# uINS_Mk1.net
KiCad netlist of a schematic drawn in EAGLE
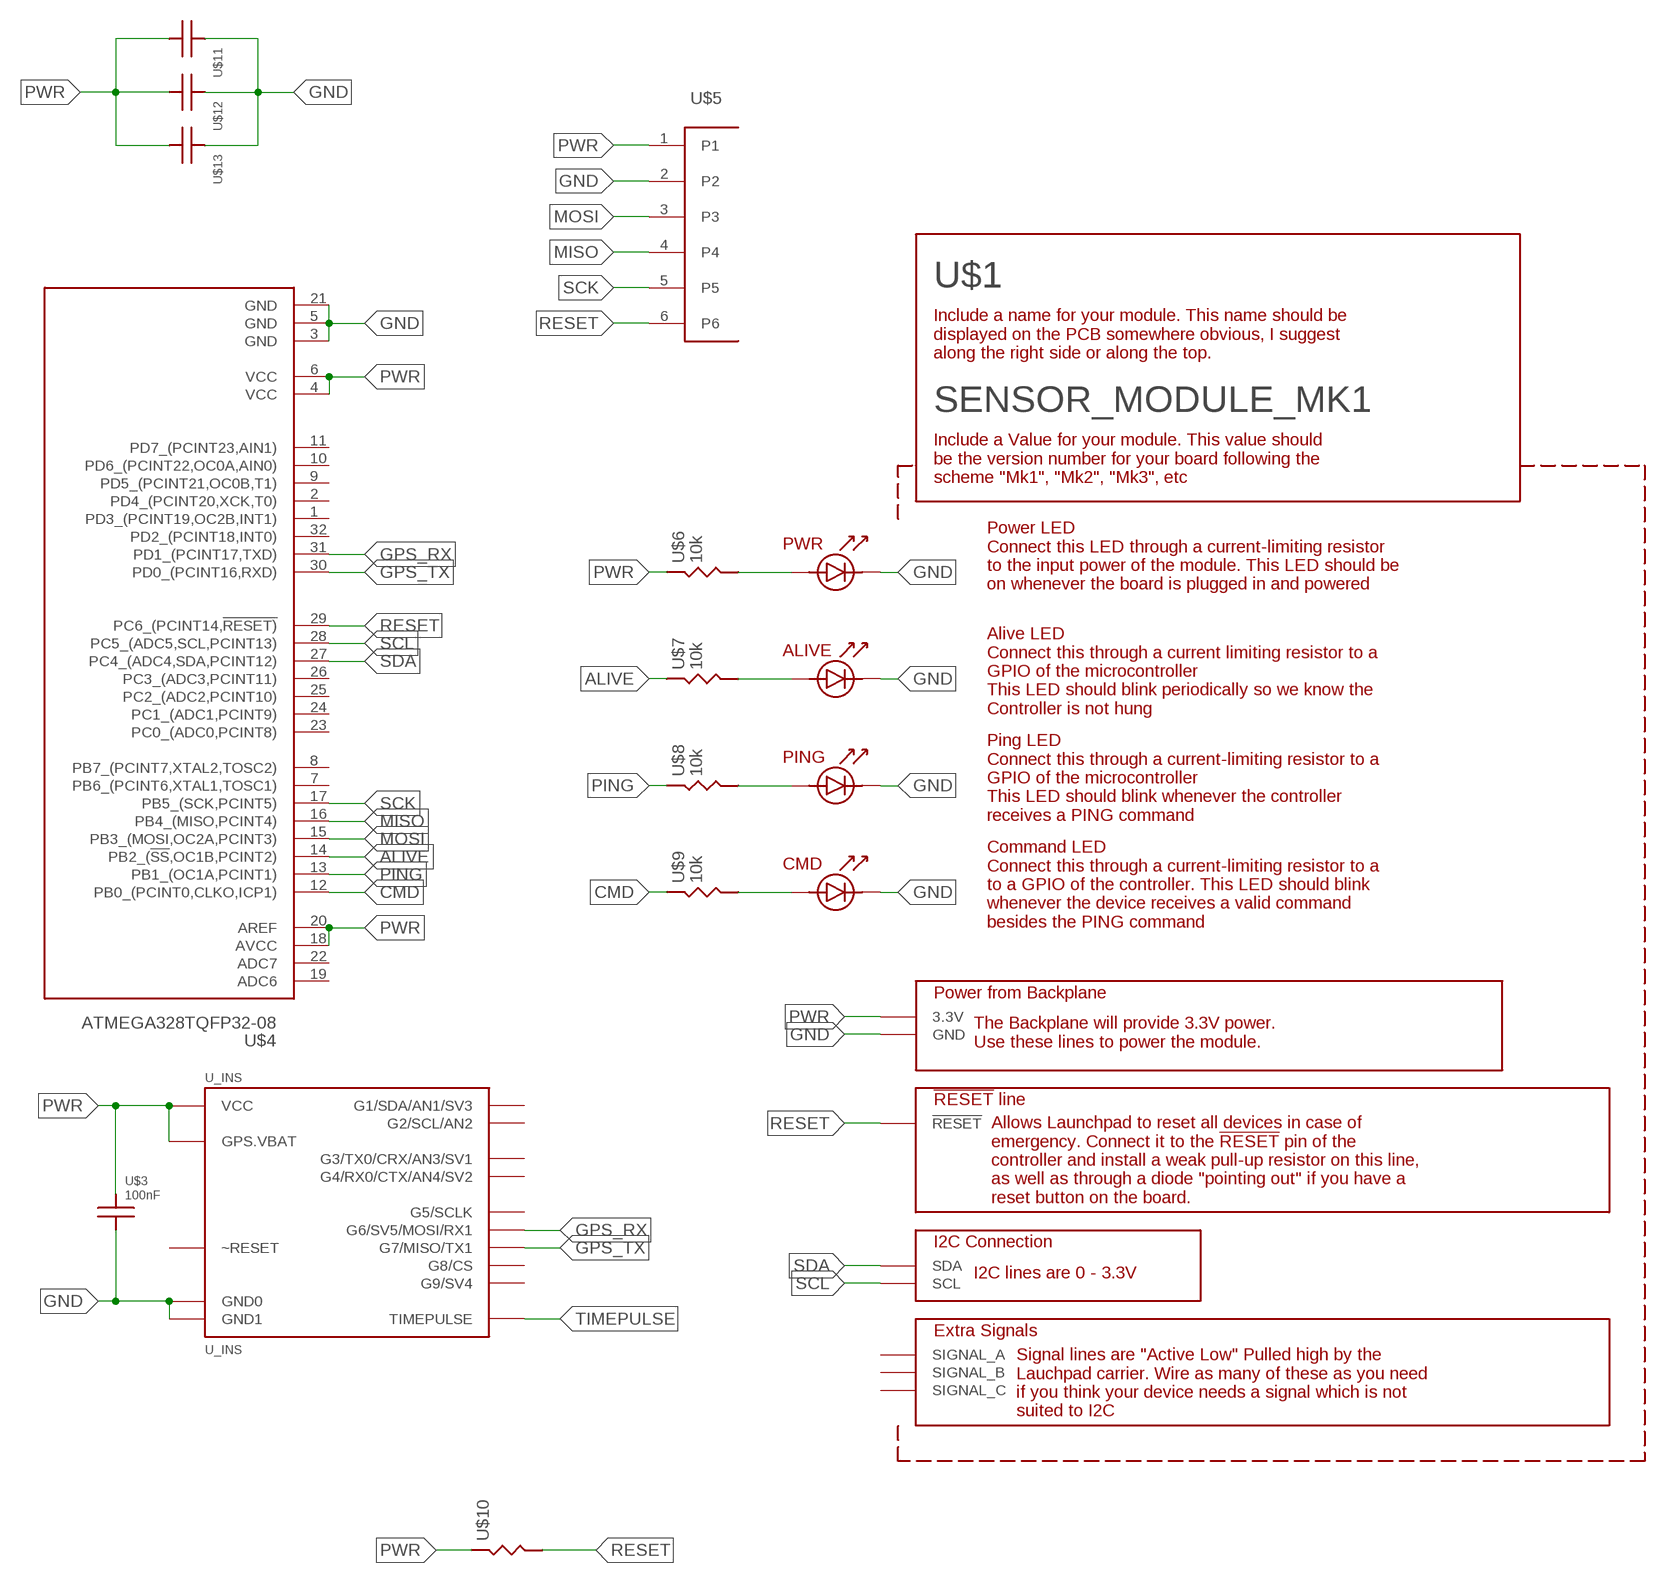
[diagram p0: schematic, sheet 1]

(export (version "E")
  (design (tool "Eeschema 10.0.6"))
  (components
    (comp (ref "U$1")
      (value "SENSOR_MODULE_MK1")
      (footprint "eagle-import:SENSOR_MODULE_MK1")
      (libsource (lib "eagle-import") (part "SENSOR_MODULE_MK1"))
    )
    (comp (ref "U$3")
      (value "100nF")
      (footprint "eagle-import:0805_STACKPOLERESISTOR")
      (libsource (lib "eagle-import") (part "CAPACITOR-UNPOLARIZED0805"))
    )
    (comp (ref "U$4")
      (value "ATMEGA328TQFP32-08")
      (footprint "eagle-import:TQFP32-08")
      (libsource (lib "eagle-import") (part "ATMEGA328TQFP32-08"))
    )
    (comp (ref "U$5")
      (value "6PIN-HEADER2X3")
      (footprint "eagle-import:6PINHEADER_CORRECT")
      (libsource (lib "eagle-import") (part "6PIN-HEADER2X3"))
    )
    (comp (ref "U$6")
      (value "10k")
      (footprint "eagle-import:0805_STACKPOLERESISTOR")
      (libsource (lib "eagle-import") (part "RESISTOR"))
    )
    (comp (ref "U$7")
      (value "10k")
      (footprint "eagle-import:0805_STACKPOLERESISTOR")
      (libsource (lib "eagle-import") (part "RESISTOR"))
    )
    (comp (ref "U$8")
      (value "10k")
      (footprint "eagle-import:0805_STACKPOLERESISTOR")
      (libsource (lib "eagle-import") (part "RESISTOR"))
    )
    (comp (ref "U$9")
      (value "10k")
      (footprint "eagle-import:0805_STACKPOLERESISTOR")
      (libsource (lib "eagle-import") (part "RESISTOR"))
    )
    (comp (ref "U$10")
      (value "RESISTOR")
      (footprint "eagle-import:0805_STACKPOLERESISTOR")
      (libsource (lib "eagle-import") (part "RESISTOR"))
    )
    (comp (ref "U$11")
      (value "CAPACITOR-UNPOLARIZED0805")
      (footprint "eagle-import:0805_STACKPOLERESISTOR")
      (libsource (lib "eagle-import") (part "CAPACITOR-UNPOLARIZED0805"))
    )
    (comp (ref "U$12")
      (value "CAPACITOR-UNPOLARIZED0805")
      (footprint "eagle-import:0805_STACKPOLERESISTOR")
      (libsource (lib "eagle-import") (part "CAPACITOR-UNPOLARIZED0805"))
    )
    (comp (ref "U$13")
      (value "CAPACITOR-UNPOLARIZED0805")
      (footprint "eagle-import:0805_STACKPOLERESISTOR")
      (libsource (lib "eagle-import") (part "CAPACITOR-UNPOLARIZED0805"))
    )
    (comp (ref "U_INS")
      (value "U_INS")
      (footprint "eagle-import:U_INS")
      (libsource (lib "eagle-import") (part "U_INS"))
    )
  )
  (nets
    (net (code "1") (name "ALIVE") (class "Default")
      (node (ref "U$4") (pin "14") (pinfunction "PB2_(~{SS,OC1B,PCINT2})_14") (pintype "bidirectional"))
      (node (ref "U$7") (pin "P$1") (pinfunction "P$1_P$1") (pintype "bidirectional"))
    )
    (net (code "2") (name "CMD") (class "Default")
      (node (ref "U$4") (pin "12") (pinfunction "PB0_(PCINT0,CLKO,ICP1)_12") (pintype "bidirectional"))
      (node (ref "U$9") (pin "P$1") (pinfunction "P$1_P$1") (pintype "bidirectional"))
    )
    (net (code "3") (name "GND") (class "Default")
      (node (ref "U$1") (pin "ALIVELED_CATHODE") (pinfunction "ALIVELED_CATHODE_ALIVELED_CATHODE") (pintype "bidirectional"))
      (node (ref "U$1") (pin "CMDLED_CATHODE") (pinfunction "CMDLED_CATHODE_CMDLED_CATHODE") (pintype "bidirectional"))
      (node (ref "U$1") (pin "GND") (pinfunction "GND_GND") (pintype "bidirectional"))
      (node (ref "U$1") (pin "PINGLED_CATHODE") (pinfunction "PINGLED_CATHODE_PINGLED_CATHODE") (pintype "bidirectional"))
      (node (ref "U$1") (pin "PWRLED_CATHODE") (pinfunction "PWRLED_CATHODE_PWRLED_CATHODE") (pintype "bidirectional"))
      (node (ref "U$11") (pin "P$1") (pinfunction "P$1_P$1") (pintype "bidirectional"))
      (node (ref "U$12") (pin "P$1") (pinfunction "P$1_P$1") (pintype "bidirectional"))
      (node (ref "U$13") (pin "P$1") (pinfunction "P$1_P$1") (pintype "bidirectional"))
      (node (ref "U$3") (pin "P$2") (pinfunction "P$2_P$2") (pintype "bidirectional"))
      (node (ref "U$4") (pin "21") (pinfunction "GND_21") (pintype "bidirectional"))
      (node (ref "U$4") (pin "3") (pinfunction "GND_3") (pintype "bidirectional"))
      (node (ref "U$4") (pin "5") (pinfunction "GND_5") (pintype "bidirectional"))
      (node (ref "U$5") (pin "2") (pinfunction "P2_2") (pintype "bidirectional"))
      (node (ref "U_INS") (pin "GND0") (pinfunction "GND0_GND0") (pintype "bidirectional"))
      (node (ref "U_INS") (pin "GND1") (pinfunction "GND1_GND1") (pintype "bidirectional"))
    )
    (net (code "4") (name "GPS_RX") (class "Default")
      (node (ref "U$4") (pin "31") (pinfunction "PD1_(PCINT17,TXD)_31") (pintype "bidirectional"))
      (node (ref "U_INS") (pin "G6/RX1/MOSI") (pinfunction "G6/SV5/MOSI/RX1_G6/RX1/MOSI") (pintype "bidirectional"))
    )
    (net (code "5") (name "GPS_TX") (class "Default")
      (node (ref "U$4") (pin "30") (pinfunction "PD0_(PCINT16,RXD)_30") (pintype "bidirectional"))
      (node (ref "U_INS") (pin "G7/TX1/MISO") (pinfunction "G7/MISO/TX1_G7/TX1/MISO") (pintype "bidirectional"))
    )
    (net (code "6") (name "MISO") (class "Default")
      (node (ref "U$4") (pin "16") (pinfunction "PB4_(MISO,PCINT4)_16") (pintype "bidirectional"))
      (node (ref "U$5") (pin "4") (pinfunction "P4_4") (pintype "bidirectional"))
    )
    (net (code "7") (name "MOSI") (class "Default")
      (node (ref "U$4") (pin "15") (pinfunction "PB3_(MOSI,OC2A,PCINT3)_15") (pintype "bidirectional"))
      (node (ref "U$5") (pin "3") (pinfunction "P3_3") (pintype "bidirectional"))
    )
    (net (code "8") (name "Net-(U$1-PadALIVELED_ANODE)") (class "Default")
      (node (ref "U$1") (pin "ALIVELED_ANODE") (pinfunction "ALIVELED_ANODE_ALIVELED_ANODE") (pintype "bidirectional"))
      (node (ref "U$7") (pin "P$2") (pinfunction "P$2_P$2") (pintype "bidirectional"))
    )
    (net (code "9") (name "Net-(U$1-PadCMDLED_ANODE)") (class "Default")
      (node (ref "U$1") (pin "CMDLED_ANODE") (pinfunction "CMDLED_ANODE_CMDLED_ANODE") (pintype "bidirectional"))
      (node (ref "U$9") (pin "P$2") (pinfunction "P$2_P$2") (pintype "bidirectional"))
    )
    (net (code "10") (name "Net-(U$1-PadPINGLED_ANODE)") (class "Default")
      (node (ref "U$1") (pin "PINGLED_ANODE") (pinfunction "PINGLED_ANODE_PINGLED_ANODE") (pintype "bidirectional"))
      (node (ref "U$8") (pin "P$2") (pinfunction "P$2_P$2") (pintype "bidirectional"))
    )
    (net (code "11") (name "Net-(U$1-PadPWRLED_ANODE)") (class "Default")
      (node (ref "U$1") (pin "PWRLED_ANODE") (pinfunction "PWRLED_ANODE_PWRLED_ANODE") (pintype "bidirectional"))
      (node (ref "U$6") (pin "P$2") (pinfunction "P$2_P$2") (pintype "bidirectional"))
    )
    (net (code "12") (name "PING") (class "Default")
      (node (ref "U$4") (pin "13") (pinfunction "PB1_(OC1A,PCINT1)_13") (pintype "bidirectional"))
      (node (ref "U$8") (pin "P$1") (pinfunction "P$1_P$1") (pintype "bidirectional"))
    )
    (net (code "13") (name "PWR") (class "Default")
      (node (ref "U$1") (pin "3P3V") (pinfunction "3.3V_3P3V") (pintype "bidirectional"))
      (node (ref "U$10") (pin "P$1") (pinfunction "P$1_P$1") (pintype "bidirectional"))
      (node (ref "U$11") (pin "P$2") (pinfunction "P$2_P$2") (pintype "bidirectional"))
      (node (ref "U$12") (pin "P$2") (pinfunction "P$2_P$2") (pintype "bidirectional"))
      (node (ref "U$13") (pin "P$2") (pinfunction "P$2_P$2") (pintype "bidirectional"))
      (node (ref "U$3") (pin "P$1") (pinfunction "P$1_P$1") (pintype "bidirectional"))
      (node (ref "U$4") (pin "18") (pinfunction "AVCC_18") (pintype "bidirectional"))
      (node (ref "U$4") (pin "20") (pinfunction "AREF_20") (pintype "bidirectional"))
      (node (ref "U$4") (pin "4") (pinfunction "VCC_4") (pintype "bidirectional"))
      (node (ref "U$4") (pin "6") (pinfunction "VCC_6") (pintype "bidirectional"))
      (node (ref "U$5") (pin "1") (pinfunction "P1_1") (pintype "bidirectional"))
      (node (ref "U$6") (pin "P$1") (pinfunction "P$1_P$1") (pintype "bidirectional"))
      (node (ref "U_INS") (pin "GPS.VBAT") (pinfunction "GPS.VBAT_GPS.VBAT") (pintype "bidirectional"))
      (node (ref "U_INS") (pin "VCC") (pinfunction "VCC_VCC") (pintype "bidirectional"))
    )
    (net (code "14") (name "RESET") (class "Default")
      (node (ref "U$1") (pin "RESET") (pinfunction "~{RESET}_RESET") (pintype "bidirectional"))
      (node (ref "U$10") (pin "P$2") (pinfunction "P$2_P$2") (pintype "bidirectional"))
      (node (ref "U$4") (pin "29") (pinfunction "PC6_(PCINT14,~{RESET})_29") (pintype "bidirectional"))
      (node (ref "U$5") (pin "6") (pinfunction "P6_6") (pintype "bidirectional"))
    )
    (net (code "15") (name "SCK") (class "Default")
      (node (ref "U$4") (pin "17") (pinfunction "PB5_(SCK,PCINT5)_17") (pintype "bidirectional"))
      (node (ref "U$5") (pin "5") (pinfunction "P5_5") (pintype "bidirectional"))
    )
    (net (code "16") (name "SCL") (class "Default")
      (node (ref "U$1") (pin "SCL") (pinfunction "SCL_SCL") (pintype "bidirectional"))
      (node (ref "U$4") (pin "28") (pinfunction "PC5_(ADC5,SCL,PCINT13)_28") (pintype "bidirectional"))
    )
    (net (code "17") (name "SDA") (class "Default")
      (node (ref "U$1") (pin "SDA") (pinfunction "SDA_SDA") (pintype "bidirectional"))
      (node (ref "U$4") (pin "27") (pinfunction "PC4_(ADC4,SDA,PCINT12)_27") (pintype "bidirectional"))
    )
    (net (code "18") (name "TIMEPULSE") (class "Default")
      (node (ref "U_INS") (pin "GPS.TIMEPULSE") (pinfunction "TIMEPULSE_GPS.TIMEPULSE") (pintype "bidirectional"))
    )
    (net (code "19") (name "unconnected-(U$1-SIGNAL_A-PadA)") (class "Default")
      (node (ref "U$1") (pin "A") (pinfunction "SIGNAL_A_A") (pintype "bidirectional"))
    )
    (net (code "20") (name "unconnected-(U$1-SIGNAL_B-PadB)") (class "Default")
      (node (ref "U$1") (pin "B") (pinfunction "SIGNAL_B_B") (pintype "bidirectional"))
    )
    (net (code "21") (name "unconnected-(U$1-SIGNAL_C-PadC)") (class "Default")
      (node (ref "U$1") (pin "C") (pinfunction "SIGNAL_C_C") (pintype "bidirectional"))
    )
    (net (code "22") (name "unconnected-(U$4-ADC6-Pad19)") (class "Default")
      (node (ref "U$4") (pin "19") (pinfunction "ADC6_19") (pintype "bidirectional"))
    )
    (net (code "23") (name "unconnected-(U$4-ADC7-Pad22)") (class "Default")
      (node (ref "U$4") (pin "22") (pinfunction "ADC7_22") (pintype "bidirectional"))
    )
    (net (code "24") (name "unconnected-(U$4-PB6_(PCINT6,XTAL1,TOSC1)-Pad7)") (class "Default")
      (node (ref "U$4") (pin "7") (pinfunction "PB6_(PCINT6,XTAL1,TOSC1)_7") (pintype "bidirectional"))
    )
    (net (code "25") (name "unconnected-(U$4-PB7_(PCINT7,XTAL2,TOSC2)-Pad8)") (class "Default")
      (node (ref "U$4") (pin "8") (pinfunction "PB7_(PCINT7,XTAL2,TOSC2)_8") (pintype "bidirectional"))
    )
    (net (code "26") (name "unconnected-(U$4-PC0_(ADC0,PCINT8)-Pad23)") (class "Default")
      (node (ref "U$4") (pin "23") (pinfunction "PC0_(ADC0,PCINT8)_23") (pintype "bidirectional"))
    )
    (net (code "27") (name "unconnected-(U$4-PC1_(ADC1,PCINT9)-Pad24)") (class "Default")
      (node (ref "U$4") (pin "24") (pinfunction "PC1_(ADC1,PCINT9)_24") (pintype "bidirectional"))
    )
    (net (code "28") (name "unconnected-(U$4-PC2_(ADC2,PCINT10)-Pad25)") (class "Default")
      (node (ref "U$4") (pin "25") (pinfunction "PC2_(ADC2,PCINT10)_25") (pintype "bidirectional"))
    )
    (net (code "29") (name "unconnected-(U$4-PC3_(ADC3,PCINT11)-Pad26)") (class "Default")
      (node (ref "U$4") (pin "26") (pinfunction "PC3_(ADC3,PCINT11)_26") (pintype "bidirectional"))
    )
    (net (code "30") (name "unconnected-(U$4-PD2_(PCINT18,INT0)-Pad32)") (class "Default")
      (node (ref "U$4") (pin "32") (pinfunction "PD2_(PCINT18,INT0)_32") (pintype "bidirectional"))
    )
    (net (code "31") (name "unconnected-(U$4-PD3_(PCINT19,OC2B,INT1)-Pad1)") (class "Default")
      (node (ref "U$4") (pin "1") (pinfunction "PD3_(PCINT19,OC2B,INT1)_1") (pintype "bidirectional"))
    )
    (net (code "32") (name "unconnected-(U$4-PD4_(PCINT20,XCK,T0)-Pad2)") (class "Default")
      (node (ref "U$4") (pin "2") (pinfunction "PD4_(PCINT20,XCK,T0)_2") (pintype "bidirectional"))
    )
    (net (code "33") (name "unconnected-(U$4-PD5_(PCINT21,OC0B,T1)-Pad9)") (class "Default")
      (node (ref "U$4") (pin "9") (pinfunction "PD5_(PCINT21,OC0B,T1)_9") (pintype "bidirectional"))
    )
    (net (code "34") (name "unconnected-(U$4-PD6_(PCINT22,OC0A,AIN0)-Pad10)") (class "Default")
      (node (ref "U$4") (pin "10") (pinfunction "PD6_(PCINT22,OC0A,AIN0)_10") (pintype "bidirectional"))
    )
    (net (code "35") (name "unconnected-(U$4-PD7_(PCINT23,AIN1)-Pad11)") (class "Default")
      (node (ref "U$4") (pin "11") (pinfunction "PD7_(PCINT23,AIN1)_11") (pintype "bidirectional"))
    )
    (net (code "36") (name "unconnected-(U_INS-G1{slash}SDA{slash}AN1{slash}SV3-PadG1{slash}SDA{slash}AN1)") (class "Default")
      (node (ref "U_INS") (pin "G1/SDA/AN1") (pinfunction "G1/SDA/AN1/SV3_G1/SDA/AN1") (pintype "bidirectional"))
    )
    (net (code "37") (name "unconnected-(U_INS-G3{slash}TX0{slash}CRX{slash}AN3{slash}SV1-PadG3{slash}TX0{slash}AN3)") (class "Default")
      (node (ref "U_INS") (pin "G3/TX0/AN3") (pinfunction "G3/TX0/CRX/AN3/SV1_G3/TX0/AN3") (pintype "bidirectional"))
    )
    (net (code "38") (name "unconnected-(U_INS-G4{slash}RX0{slash}CTX{slash}AN4{slash}SV2-PadG4{slash}RX0{slash}AN4)") (class "Default")
      (node (ref "U_INS") (pin "G4/RX0/AN4") (pinfunction "G4/RX0/CTX/AN4/SV2_G4/RX0/AN4") (pintype "bidirectional"))
    )
    (net (code "39") (name "unconnected-(U_INS-G9{slash}SV4-PadG9)") (class "Default")
      (node (ref "U_INS") (pin "G9") (pinfunction "G9/SV4_G9") (pintype "bidirectional"))
    )
    (net (code "40") (name "unconnected-(U_INS-PadG2{slash}SCL{slash}AN2)") (class "Default")
      (node (ref "U_INS") (pin "G2/SCL/AN2") (pinfunction "G2/SCL/AN2_G2/SCL/AN2") (pintype "bidirectional"))
    )
    (net (code "41") (name "unconnected-(U_INS-PadG5{slash}SCLK)") (class "Default")
      (node (ref "U_INS") (pin "G5/SCLK") (pinfunction "G5/SCLK_G5/SCLK") (pintype "bidirectional"))
    )
    (net (code "42") (name "unconnected-(U_INS-PadG8{slash}CS)") (class "Default")
      (node (ref "U_INS") (pin "G8/CS") (pinfunction "G8/CS_G8/CS") (pintype "bidirectional"))
    )
    (net (code "43") (name "unconnected-(U_INS-~{RESET}-PadN.RESET)") (class "Default")
      (node (ref "U_INS") (pin "N.RESET") (pinfunction "~{RESET}_N.RESET") (pintype "bidirectional"))
    )
  )
)
